# Sheet.net
KiCad netlist of a schematic drawn in Altium Designer
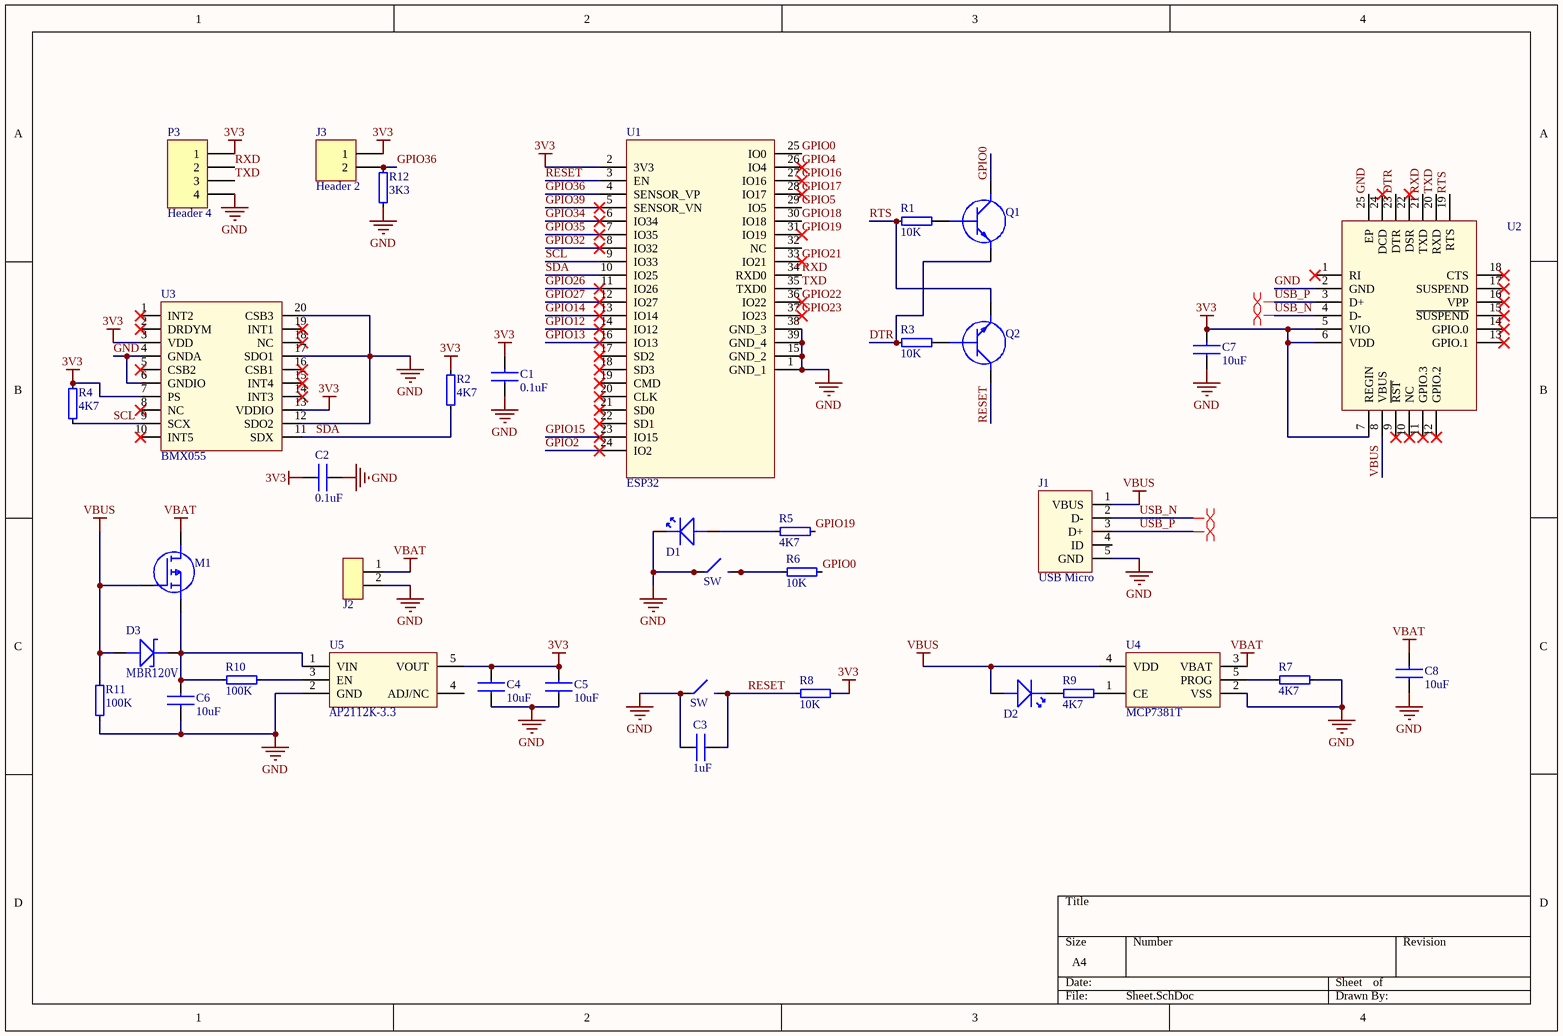
[diagram p0: Sheet.SchDoc]

(export (version "E")
  (design (tool "Eeschema 10.0.6"))
  (components
    (comp (ref "C1")
      (value "0.1uF")
      (footprint "0402 Capacitor")
      (fields (field (name "LCSC PART #") "C307331"))
      (libsource (lib "altium-import") (part "root_3_0402 Capacitor_"))
    )
    (comp (ref "C2")
      (value "0.1uF")
      (footprint "0402 Capacitor")
      (fields (field (name "LCSC PART #") "C307331"))
      (libsource (lib "altium-import") (part "root_0_0402 Capacitor_"))
    )
    (comp (ref "C3")
      (value "1uF")
      (footprint "0402 Capacitor")
      (fields (field (name "LCSC PART #") "C52923"))
      (libsource (lib "altium-import") (part "root_2_0402 Capacitor_"))
    )
    (comp (ref "C4")
      (value "10uF")
      (footprint "0402 Capacitor")
      (fields (field (name "LCSC PART #") "C15525"))
      (libsource (lib "altium-import") (part "root_1_0402 Capacitor_"))
    )
    (comp (ref "C5")
      (value "10uF")
      (footprint "0402 Capacitor")
      (fields (field (name "LCSC PART #") "C15525"))
      (libsource (lib "altium-import") (part "root_1_0402 Capacitor_"))
    )
    (comp (ref "C6")
      (value "10uF")
      (footprint "0402 Capacitor")
      (fields (field (name "LCSC PART #") "C15525"))
      (libsource (lib "altium-import") (part "root_1_0402 Capacitor_"))
    )
    (comp (ref "C7")
      (value "10uF")
      (footprint "0402 Capacitor")
      (fields (field (name "LCSC PART #") "C15525"))
      (libsource (lib "altium-import") (part "root_3_0402 Capacitor_"))
    )
    (comp (ref "C8")
      (value "10uF")
      (footprint "0402 Capacitor")
      (fields (field (name "LCSC PART #") "C15525"))
      (libsource (lib "altium-import") (part "root_3_0402 Capacitor_"))
    )
    (comp (ref "D1")
      (value "0805 LED")
      (footprint "0805 LED")
      (fields (field (name "LCSC PART #") "C84256"))
      (libsource (lib "ESP32_Sch_Lib") (part "0805 LED"))
    )
    (comp (ref "D2")
      (value "0805 LED")
      (footprint "0805 LED")
      (fields (field (name "LCSC PART #") "C84256"))
      (libsource (lib "ESP32_Sch_Lib") (part "0805 LED"))
    )
    (comp (ref "D3")
      (value "‎MBR120V")
      (footprint "Shotcky")
      (fields (field (name "LCSC PART #") "C130880"))
      (libsource (lib "ESP32_Sch_Lib") (part "Shotky Diode"))
    )
    (comp (ref "J1")
      (value "USB Micro")
      (footprint "USB Micro")
      (libsource (lib "altium-import") (part "root_0_USB Micro_"))
    )
    (comp (ref "J2")
      (value "JSTPH")
      (footprint "JSTPH")
      (libsource (lib "altium-import") (part "root_0_JSTPH_"))
    )
    (comp (ref "J3")
      (value "Header 2")
      (footprint "HDR1X2")
      (description "Header, 2-Pin")
      (fields (field (name "PUBLISHER") "Altium Limited"))
      (libsource (lib "Miscellaneous Connectors") (part "Header 2"))
    )
    (comp (ref "M1")
      (value "DMG3415U")
      (footprint "DMG3415U")
      (fields (field (name "LCSC PART #") "C96616"))
      (libsource (lib "altium-import") (part "root_0_DMG3415U_"))
    )
    (comp (ref "P3")
      (value "Header 4")
      (footprint "HDR1X4")
      (description "Header, 4-Pin")
      (fields (field (name "PUBLISHER") "Altium Limited"))
      (libsource (lib "Miscellaneous Connectors") (part "Header 4"))
    )
    (comp (ref "Q1")
      (value "MMBT2222A")
      (footprint "MMBR2222A")
      (fields (field (name "LCSC PART #") "C83939"))
      (libsource (lib "altium-import") (part "root_0_MMBT2222A_"))
    )
    (comp (ref "Q2")
      (value "MMBT2222A")
      (footprint "MMBR2222A")
      (fields (field (name "LCSC PART #") "C83939"))
      (libsource (lib "altium-import") (part "root_2_mirrored_MMBT2222A_"))
    )
    (comp (ref "R1")
      (value "10K")
      (footprint "0402 Resistor")
      (fields (field (name "LCSC PART #") "C25744"))
      (libsource (lib "altium-import") (part "root_0_0402 Resistor_"))
    )
    (comp (ref "R2")
      (value "4K7")
      (footprint "0402 Resistor")
      (fields (field (name "LCSC PART #") "C25900"))
      (libsource (lib "altium-import") (part "root_1_0402 Resistor_"))
    )
    (comp (ref "R3")
      (value "10K")
      (footprint "0402 Resistor")
      (fields (field (name "LCSC PART #") "C25744"))
      (libsource (lib "altium-import") (part "root_0_0402 Resistor_"))
    )
    (comp (ref "R4")
      (value "4K7")
      (footprint "0402 Resistor")
      (fields (field (name "LCSC PART #") "C25900"))
      (libsource (lib "altium-import") (part "root_1_0402 Resistor_"))
    )
    (comp (ref "R5")
      (value "4K7")
      (footprint "0402 Resistor")
      (fields (field (name "LCSC PART #") "C25900"))
      (libsource (lib "altium-import") (part "root_0_0402 Resistor_"))
    )
    (comp (ref "R6")
      (value "10K")
      (footprint "0402 Resistor")
      (fields (field (name "LCSC PART #") "C25744"))
      (libsource (lib "altium-import") (part "root_0_0402 Resistor_"))
    )
    (comp (ref "R7")
      (value "4K7")
      (footprint "0402 Resistor")
      (fields (field (name "LCSC PART #") "C25900"))
      (libsource (lib "altium-import") (part "root_0_0402 Resistor_"))
    )
    (comp (ref "R8")
      (value "10K")
      (footprint "0402 Resistor")
      (fields (field (name "LCSC PART #") "C25744"))
      (libsource (lib "altium-import") (part "root_0_0402 Resistor_"))
    )
    (comp (ref "R9")
      (value "4K7")
      (footprint "0402 Resistor")
      (fields (field (name "LCSC PART #") "C25900"))
      (libsource (lib "altium-import") (part "root_0_0402 Resistor_"))
    )
    (comp (ref "R10")
      (value "100K")
      (footprint "0402 Resistor")
      (fields (field (name "LCSC PART #") "C25741"))
      (libsource (lib "altium-import") (part "root_0_0402 Resistor_"))
    )
    (comp (ref "R11")
      (value "100K")
      (footprint "0402 Resistor")
      (fields (field (name "LCSC PART #") "C25741"))
      (libsource (lib "altium-import") (part "root_1_0402 Resistor_"))
    )
    (comp (ref "R12")
      (value "3K3")
      (footprint "0402 Resistor")
      (fields (field (name "LCSC PART #") "C25890"))
      (libsource (lib "altium-import") (part "root_1_0402 Resistor_"))
    )
    (comp (ref "SW1")
      (value "SW")
      (footprint "Tall Switch")
      (libsource (lib "ESP32_Sch_Lib") (part "Switch"))
    )
    (comp (ref "SW2")
      (value "SW")
      (footprint "Tall Switch")
      (libsource (lib "ESP32_Sch_Lib") (part "Switch"))
    )
    (comp (ref "U1") (value "ESP32") (footprint "ESP32SMD") (libsource (lib "ESP32_Sch_Lib") (part "ESP32")))
    (comp (ref "U2")
      (value "CP2104")
      (footprint "CP2104")
      (fields (field (name "LCSC PART #") "C47742"))
      (libsource (lib "altium-import") (part "root_0_CP2104_"))
    )
    (comp (ref "U3")
      (value "BMX055")
      (footprint "BMX055")
      (fields (field (name "LCSC PART #") "C94022"))
      (libsource (lib "ESP32_Sch_Lib") (part "BMX055"))
    )
    (comp (ref "U4")
      (value "MCP7381T")
      (footprint "MCP73831T")
      (fields (field (name "LCSC PART #") "C424093"))
      (libsource (lib "altium-import") (part "root_0_MCP7381T_"))
    )
    (comp (ref "U5")
      (value "‎AP2112K-3.3")
      (footprint "3V3 Reg")
      (fields (field (name "LCSC PART #") "C51118"))
      (libsource (lib "ESP32_Sch_Lib") (part "3V3 Reg"))
    )
  )
  (nets
    (net (code "1") (name "/DTR") (class "Default")
      (node (ref "Q1") (pin "2") (pinfunction "E_2") (pintype "passive"))
      (node (ref "R3") (pin "1") (pinfunction "1_1") (pintype "passive"))
      (node (ref "U2") (pin "23") (pinfunction "DTR_23") (pintype "passive"))
    )
    (net (code "2") (name "/GPIO0") (class "Default")
      (node (ref "Q1") (pin "3") (pinfunction "C_3") (pintype "passive"))
      (node (ref "R6") (pin "2") (pinfunction "2_2") (pintype "passive"))
      (node (ref "U1") (pin "25") (pinfunction "IO0_25") (pintype "passive"))
    )
    (net (code "3") (name "/GPIO2") (class "Default")
      (node (ref "U1") (pin "24") (pinfunction "IO2_24") (pintype "passive+no_connect"))
    )
    (net (code "4") (name "/GPIO4") (class "Default")
      (node (ref "U1") (pin "26") (pinfunction "IO4_26") (pintype "passive+no_connect"))
    )
    (net (code "5") (name "/GPIO5") (class "Default")
      (node (ref "U1") (pin "29") (pinfunction "IO5_29") (pintype "passive"))
    )
    (net (code "6") (name "/GPIO12") (class "Default")
      (node (ref "U1") (pin "14") (pinfunction "IO12_14") (pintype "passive+no_connect"))
    )
    (net (code "7") (name "/GPIO13") (class "Default")
      (node (ref "U1") (pin "16") (pinfunction "IO13_16") (pintype "passive+no_connect"))
    )
    (net (code "8") (name "/GPIO14") (class "Default")
      (node (ref "U1") (pin "13") (pinfunction "IO14_13") (pintype "passive+no_connect"))
    )
    (net (code "9") (name "/GPIO15") (class "Default")
      (node (ref "U1") (pin "23") (pinfunction "IO15_23") (pintype "passive+no_connect"))
    )
    (net (code "10") (name "/GPIO16") (class "Default")
      (node (ref "U1") (pin "27") (pinfunction "IO16_27") (pintype "passive+no_connect"))
    )
    (net (code "11") (name "/GPIO17") (class "Default")
      (node (ref "U1") (pin "28") (pinfunction "IO17_28") (pintype "passive+no_connect"))
    )
    (net (code "12") (name "/GPIO18") (class "Default")
      (node (ref "U1") (pin "30") (pinfunction "IO18_30") (pintype "passive"))
    )
    (net (code "13") (name "/GPIO19") (class "Default")
      (node (ref "R5") (pin "2") (pinfunction "2_2") (pintype "passive"))
      (node (ref "U1") (pin "31") (pinfunction "IO19_31") (pintype "passive"))
    )
    (net (code "14") (name "/GPIO21") (class "Default")
      (node (ref "U1") (pin "33") (pinfunction "IO21_33") (pintype "passive+no_connect"))
    )
    (net (code "15") (name "/GPIO22") (class "Default")
      (node (ref "U1") (pin "36") (pinfunction "IO22_36") (pintype "passive+no_connect"))
    )
    (net (code "16") (name "/GPIO23") (class "Default")
      (node (ref "U1") (pin "37") (pinfunction "IO23_37") (pintype "passive+no_connect"))
    )
    (net (code "17") (name "/GPIO26") (class "Default")
      (node (ref "U1") (pin "11") (pinfunction "IO26_11") (pintype "passive+no_connect"))
    )
    (net (code "18") (name "/GPIO27") (class "Default")
      (node (ref "U1") (pin "12") (pinfunction "IO27_12") (pintype "passive+no_connect"))
    )
    (net (code "19") (name "/GPIO32") (class "Default")
      (node (ref "U1") (pin "8") (pinfunction "IO32_8") (pintype "passive+no_connect"))
    )
    (net (code "20") (name "/GPIO34") (class "Default")
      (node (ref "U1") (pin "6") (pinfunction "IO34_6") (pintype "passive+no_connect"))
    )
    (net (code "21") (name "/GPIO35") (class "Default")
      (node (ref "U1") (pin "7") (pinfunction "IO35_7") (pintype "passive+no_connect"))
    )
    (net (code "22") (name "/GPIO36") (class "Default")
      (node (ref "J3") (pin "2") (pinfunction "2_2") (pintype "passive"))
      (node (ref "R12") (pin "2") (pinfunction "2_2") (pintype "passive"))
      (node (ref "U1") (pin "4") (pinfunction "SENSOR_VP_4") (pintype "passive"))
    )
    (net (code "23") (name "/GPIO39") (class "Default")
      (node (ref "U1") (pin "5") (pinfunction "SENSOR_VN_5") (pintype "passive+no_connect"))
    )
    (net (code "24") (name "/RESET") (class "Default")
      (node (ref "C3") (pin "1") (pinfunction "1_1") (pintype "passive"))
      (node (ref "Q2") (pin "3") (pinfunction "C_3") (pintype "passive"))
      (node (ref "R8") (pin "1") (pinfunction "1_1") (pintype "passive"))
      (node (ref "SW2") (pin "3") (pintype "passive"))
      (node (ref "SW2") (pin "4") (pintype "passive"))
      (node (ref "U1") (pin "3") (pinfunction "EN_3") (pintype "passive"))
    )
    (net (code "25") (name "/RTS") (class "Default")
      (node (ref "Q2") (pin "2") (pinfunction "E_2") (pintype "passive"))
      (node (ref "R1") (pin "1") (pinfunction "1_1") (pintype "passive"))
      (node (ref "U2") (pin "19") (pinfunction "RTS_19") (pintype "passive"))
    )
    (net (code "26") (name "/RXD") (class "Default")
      (node (ref "P3") (pin "2") (pinfunction "2_2") (pintype "passive"))
      (node (ref "U1") (pin "34") (pinfunction "RXD0_34") (pintype "passive"))
      (node (ref "U2") (pin "21") (pinfunction "TXD_21") (pintype "passive"))
    )
    (net (code "27") (name "/SCL") (class "Default")
      (node (ref "R4") (pin "1") (pinfunction "1_1") (pintype "passive"))
      (node (ref "U1") (pin "9") (pinfunction "IO33_9") (pintype "passive"))
      (node (ref "U3") (pin "9") (pinfunction "SCX_9") (pintype "passive"))
    )
    (net (code "28") (name "/SDA") (class "Default")
      (node (ref "R2") (pin "1") (pinfunction "1_1") (pintype "passive"))
      (node (ref "U1") (pin "10") (pinfunction "IO25_10") (pintype "passive"))
      (node (ref "U3") (pin "11") (pinfunction "SDX_11") (pintype "passive"))
    )
    (net (code "29") (name "/TXD") (class "Default")
      (node (ref "P3") (pin "3") (pinfunction "3_3") (pintype "passive"))
      (node (ref "U1") (pin "35") (pinfunction "TXD0_35") (pintype "passive"))
      (node (ref "U2") (pin "20") (pinfunction "RXD_20") (pintype "passive"))
    )
    (net (code "30") (name "/USB_N") (class "Default")
      (node (ref "J1") (pin "2") (pinfunction "D-_2") (pintype "passive"))
      (node (ref "U2") (pin "4") (pinfunction "D-_4") (pintype "passive"))
    )
    (net (code "31") (name "/USB_P") (class "Default")
      (node (ref "J1") (pin "3") (pinfunction "D+_3") (pintype "passive"))
      (node (ref "U2") (pin "3") (pinfunction "D+_3") (pintype "passive"))
    )
    (net (code "32") (name "3V3") (class "Default")
      (node (ref "C1") (pin "1") (pinfunction "1_1") (pintype "passive"))
      (node (ref "C2") (pin "1") (pinfunction "1_1") (pintype "passive"))
      (node (ref "C4") (pin "2") (pinfunction "2_2") (pintype "passive"))
      (node (ref "C5") (pin "2") (pinfunction "2_2") (pintype "passive"))
      (node (ref "C7") (pin "1") (pinfunction "1_1") (pintype "passive"))
      (node (ref "J3") (pin "1") (pinfunction "1_1") (pintype "passive"))
      (node (ref "P3") (pin "1") (pinfunction "1_1") (pintype "passive"))
      (node (ref "R2") (pin "2") (pinfunction "2_2") (pintype "passive"))
      (node (ref "R4") (pin "2") (pinfunction "2_2") (pintype "passive"))
      (node (ref "R8") (pin "2") (pinfunction "2_2") (pintype "passive"))
      (node (ref "U1") (pin "2") (pinfunction "3V3_2") (pintype "passive"))
      (node (ref "U2") (pin "5") (pinfunction "VIO_5") (pintype "passive"))
      (node (ref "U2") (pin "6") (pinfunction "VDD_6") (pintype "passive"))
      (node (ref "U2") (pin "7") (pinfunction "REGIN_7") (pintype "passive"))
      (node (ref "U3") (pin "13") (pinfunction "VDDIO_13") (pintype "passive"))
      (node (ref "U3") (pin "3") (pinfunction "VDD_3") (pintype "passive"))
      (node (ref "U3") (pin "7") (pinfunction "PS_7") (pintype "passive"))
      (node (ref "U5") (pin "5") (pinfunction "VOUT_5") (pintype "passive"))
    )
    (net (code "33") (name "GND") (class "Default")
      (node (ref "C1") (pin "2") (pinfunction "2_2") (pintype "passive"))
      (node (ref "C2") (pin "2") (pinfunction "2_2") (pintype "passive"))
      (node (ref "C3") (pin "2") (pinfunction "2_2") (pintype "passive"))
      (node (ref "C4") (pin "1") (pinfunction "1_1") (pintype "passive"))
      (node (ref "C5") (pin "1") (pinfunction "1_1") (pintype "passive"))
      (node (ref "C6") (pin "1") (pinfunction "1_1") (pintype "passive"))
      (node (ref "C7") (pin "2") (pinfunction "2_2") (pintype "passive"))
      (node (ref "C8") (pin "2") (pinfunction "2_2") (pintype "passive"))
      (node (ref "D1") (pin "1") (pinfunction "1_1") (pintype "passive"))
      (node (ref "J1") (pin "5") (pinfunction "GND_5") (pintype "passive"))
      (node (ref "J2") (pin "2") (pinfunction "2_2") (pintype "passive"))
      (node (ref "P3") (pin "4") (pinfunction "4_4") (pintype "passive"))
      (node (ref "R11") (pin "1") (pinfunction "1_1") (pintype "passive"))
      (node (ref "R12") (pin "1") (pinfunction "1_1") (pintype "passive"))
      (node (ref "R7") (pin "2") (pinfunction "2_2") (pintype "passive"))
      (node (ref "SW1") (pin "1") (pintype "passive"))
      (node (ref "SW1") (pin "2") (pintype "passive"))
      (node (ref "SW2") (pin "1") (pintype "passive"))
      (node (ref "SW2") (pin "2") (pintype "passive"))
      (node (ref "U1") (pin "1") (pinfunction "GND_1_1") (pintype "passive"))
      (node (ref "U1") (pin "15") (pinfunction "GND_2_15") (pintype "passive"))
      (node (ref "U1") (pin "38") (pinfunction "GND_3_38") (pintype "passive"))
      (node (ref "U1") (pin "39") (pinfunction "GND_4_39") (pintype "passive"))
      (node (ref "U2") (pin "2") (pinfunction "GND_2") (pintype "passive"))
      (node (ref "U2") (pin "25") (pinfunction "EP_25") (pintype "passive"))
      (node (ref "U3") (pin "12") (pinfunction "SDO2_12") (pintype "passive"))
      (node (ref "U3") (pin "17") (pinfunction "SDO1_17") (pintype "passive"))
      (node (ref "U3") (pin "20") (pinfunction "CSB3_20") (pintype "passive"))
      (node (ref "U3") (pin "4") (pinfunction "GNDA_4") (pintype "passive"))
      (node (ref "U3") (pin "6") (pinfunction "GNDIO_6") (pintype "passive"))
      (node (ref "U4") (pin "2") (pinfunction "VSS_2") (pintype "power_in"))
      (node (ref "U5") (pin "2") (pinfunction "GND_2") (pintype "passive"))
    )
    (net (code "34") (name "Net-(D1-Pad2)") (class "Default")
      (node (ref "D1") (pin "2") (pinfunction "2_2") (pintype "passive"))
      (node (ref "R5") (pin "1") (pinfunction "1_1") (pintype "passive"))
    )
    (net (code "35") (name "Net-(D2-Pad1)") (class "Default")
      (node (ref "D2") (pin "1") (pinfunction "1_1") (pintype "passive"))
      (node (ref "R9") (pin "1") (pinfunction "1_1") (pintype "passive"))
    )
    (net (code "36") (name "Net-(M1-S)") (class "Default")
      (node (ref "C6") (pin "2") (pinfunction "2_2") (pintype "passive"))
      (node (ref "D3") (pin "1") (pinfunction "1_1") (pintype "passive"))
      (node (ref "M1") (pin "2") (pinfunction "S_2") (pintype "passive"))
      (node (ref "R10") (pin "1") (pinfunction "1_1") (pintype "passive"))
      (node (ref "U5") (pin "1") (pinfunction "VIN_1") (pintype "passive"))
    )
    (net (code "37") (name "Net-(Q1-B)") (class "Default")
      (node (ref "Q1") (pin "1") (pinfunction "B_1") (pintype "passive"))
      (node (ref "R1") (pin "2") (pinfunction "2_2") (pintype "passive"))
    )
    (net (code "38") (name "Net-(Q2-B)") (class "Default")
      (node (ref "Q2") (pin "1") (pinfunction "B_1") (pintype "passive"))
      (node (ref "R3") (pin "2") (pinfunction "2_2") (pintype "passive"))
    )
    (net (code "39") (name "Net-(R6-Pad1)") (class "Default")
      (node (ref "R6") (pin "1") (pinfunction "1_1") (pintype "passive"))
      (node (ref "SW1") (pin "3") (pintype "passive"))
      (node (ref "SW1") (pin "4") (pintype "passive"))
    )
    (net (code "40") (name "Net-(U4-CE)") (class "Default")
      (node (ref "R9") (pin "2") (pinfunction "2_2") (pintype "passive"))
      (node (ref "U4") (pin "1") (pinfunction "CE_1") (pintype "passive"))
    )
    (net (code "41") (name "Net-(U4-PROG)") (class "Default")
      (node (ref "R7") (pin "1") (pinfunction "1_1") (pintype "passive"))
      (node (ref "U4") (pin "5") (pinfunction "PROG_5") (pintype "passive"))
    )
    (net (code "42") (name "Net-(U5-EN)") (class "Default")
      (node (ref "R10") (pin "2") (pinfunction "2_2") (pintype "passive"))
      (node (ref "U5") (pin "3") (pinfunction "EN_3") (pintype "passive"))
    )
    (net (code "43") (name "VBAT") (class "Default")
      (node (ref "C8") (pin "1") (pinfunction "1_1") (pintype "passive"))
      (node (ref "J2") (pin "1") (pinfunction "1_1") (pintype "passive"))
      (node (ref "M1") (pin "3") (pinfunction "D_3") (pintype "passive"))
      (node (ref "U4") (pin "3") (pinfunction "VBAT_3") (pintype "passive"))
    )
    (net (code "44") (name "VBUS") (class "Default")
      (node (ref "D2") (pin "2") (pinfunction "2_2") (pintype "passive"))
      (node (ref "D3") (pin "2") (pinfunction "2_2") (pintype "passive"))
      (node (ref "J1") (pin "1") (pinfunction "VBUS_1") (pintype "passive"))
      (node (ref "M1") (pin "1") (pinfunction "G_1") (pintype "passive"))
      (node (ref "R11") (pin "2") (pinfunction "2_2") (pintype "passive"))
      (node (ref "U2") (pin "8") (pinfunction "VBUS_8") (pintype "passive"))
      (node (ref "U4") (pin "4") (pinfunction "VDD_4") (pintype "power_in"))
    )
    (net (code "45") (name "unconnected-(J1-ID-Pad4)") (class "Default")
      (node (ref "J1") (pin "4") (pinfunction "ID_4") (pintype "passive"))
    )
    (net (code "46") (name "unconnected-(U1-CLK-Pad20)") (class "Default")
      (node (ref "U1") (pin "20") (pinfunction "CLK_20") (pintype "passive+no_connect"))
    )
    (net (code "47") (name "unconnected-(U1-CMD-Pad19)") (class "Default")
      (node (ref "U1") (pin "19") (pinfunction "CMD_19") (pintype "passive+no_connect"))
    )
    (net (code "48") (name "unconnected-(U1-NC-Pad32)") (class "Default")
      (node (ref "U1") (pin "32") (pinfunction "NC_32") (pintype "passive"))
    )
    (net (code "49") (name "unconnected-(U1-SD0-Pad21)") (class "Default")
      (node (ref "U1") (pin "21") (pinfunction "SD0_21") (pintype "passive+no_connect"))
    )
    (net (code "50") (name "unconnected-(U1-SD1-Pad22)") (class "Default")
      (node (ref "U1") (pin "22") (pinfunction "SD1_22") (pintype "passive+no_connect"))
    )
    (net (code "51") (name "unconnected-(U1-SD2-Pad17)") (class "Default")
      (node (ref "U1") (pin "17") (pinfunction "SD2_17") (pintype "passive+no_connect"))
    )
    (net (code "52") (name "unconnected-(U1-SD3-Pad18)") (class "Default")
      (node (ref "U1") (pin "18") (pinfunction "SD3_18") (pintype "passive+no_connect"))
    )
    (net (code "53") (name "unconnected-(U2-CTS-Pad18)") (class "Default")
      (node (ref "U2") (pin "18") (pinfunction "CTS_18") (pintype "passive+no_connect"))
    )
    (net (code "54") (name "unconnected-(U2-DCD-Pad24)") (class "Default")
      (node (ref "U2") (pin "24") (pinfunction "DCD_24") (pintype "passive+no_connect"))
    )
    (net (code "55") (name "unconnected-(U2-DSR-Pad22)") (class "Default")
      (node (ref "U2") (pin "22") (pinfunction "DSR_22") (pintype "passive+no_connect"))
    )
    (net (code "56") (name "unconnected-(U2-GPIO.0-Pad14)") (class "Default")
      (node (ref "U2") (pin "14") (pinfunction "GPIO.0_14") (pintype "passive+no_connect"))
    )
    (net (code "57") (name "unconnected-(U2-GPIO.1-Pad13)") (class "Default")
      (node (ref "U2") (pin "13") (pinfunction "GPIO.1_13") (pintype "passive+no_connect"))
    )
    (net (code "58") (name "unconnected-(U2-GPIO.2-Pad12)") (class "Default")
      (node (ref "U2") (pin "12") (pinfunction "GPIO.2_12") (pintype "passive+no_connect"))
    )
    (net (code "59") (name "unconnected-(U2-GPIO.3-Pad11)") (class "Default")
      (node (ref "U2") (pin "11") (pinfunction "GPIO.3_11") (pintype "passive+no_connect"))
    )
    (net (code "60") (name "unconnected-(U2-NC-Pad10)") (class "Default")
      (node (ref "U2") (pin "10") (pinfunction "NC_10") (pintype "passive+no_connect"))
    )
    (net (code "61") (name "unconnected-(U2-RI-Pad1)") (class "Default")
      (node (ref "U2") (pin "1") (pinfunction "RI_1") (pintype "passive+no_connect"))
    )
    (net (code "62") (name "unconnected-(U2-SUSPEND-Pad17)") (class "Default")
      (node (ref "U2") (pin "17") (pinfunction "SUSPEND_17") (pintype "passive+no_connect"))
    )
    (net (code "63") (name "unconnected-(U2-VPP-Pad16)") (class "Default")
      (node (ref "U2") (pin "16") (pinfunction "VPP_16") (pintype "passive+no_connect"))
    )
    (net (code "64") (name "unconnected-(U2-~{RST}-Pad9)") (class "Default")
      (node (ref "U2") (pin "9") (pinfunction "~{RST}_9") (pintype "passive+no_connect"))
    )
    (net (code "65") (name "unconnected-(U2-~{SUSPEND}-Pad15)") (class "Default")
      (node (ref "U2") (pin "15") (pinfunction "~{SUSPEND}_15") (pintype "passive+no_connect"))
    )
    (net (code "66") (name "unconnected-(U3-CSB1-Pad16)") (class "Default")
      (node (ref "U3") (pin "16") (pinfunction "CSB1_16") (pintype "passive+no_connect"))
    )
    (net (code "67") (name "unconnected-(U3-CSB2-Pad5)") (class "Default")
      (node (ref "U3") (pin "5") (pinfunction "CSB2_5") (pintype "passive+no_connect"))
    )
    (net (code "68") (name "unconnected-(U3-DRDYM-Pad2)") (class "Default")
      (node (ref "U3") (pin "2") (pinfunction "DRDYM_2") (pintype "passive+no_connect"))
    )
    (net (code "69") (name "unconnected-(U3-INT1-Pad19)") (class "Default")
      (node (ref "U3") (pin "19") (pinfunction "INT1_19") (pintype "passive+no_connect"))
    )
    (net (code "70") (name "unconnected-(U3-INT2-Pad1)") (class "Default")
      (node (ref "U3") (pin "1") (pinfunction "INT2_1") (pintype "passive+no_connect"))
    )
    (net (code "71") (name "unconnected-(U3-INT3-Pad14)") (class "Default")
      (node (ref "U3") (pin "14") (pinfunction "INT3_14") (pintype "passive+no_connect"))
    )
    (net (code "72") (name "unconnected-(U3-INT4-Pad15)") (class "Default")
      (node (ref "U3") (pin "15") (pinfunction "INT4_15") (pintype "passive+no_connect"))
    )
    (net (code "73") (name "unconnected-(U3-INT5-Pad10)") (class "Default")
      (node (ref "U3") (pin "10") (pinfunction "INT5_10") (pintype "passive+no_connect"))
    )
    (net (code "74") (name "unconnected-(U3-NC-Pad8)") (class "Default")
      (node (ref "U3") (pin "8") (pinfunction "NC_8") (pintype "passive+no_connect"))
    )
    (net (code "75") (name "unconnected-(U3-NC-Pad18)") (class "Default")
      (node (ref "U3") (pin "18") (pinfunction "NC_18") (pintype "passive+no_connect"))
    )
    (net (code "76") (name "unconnected-(U5-ADJ{slash}NC-Pad4)") (class "Default")
      (node (ref "U5") (pin "4") (pinfunction "ADJ/NC_4") (pintype "passive"))
    )
  )
)
